# ArduinoDigitalCommsShield.net
KiCad netlist of a schematic drawn in EAGLE
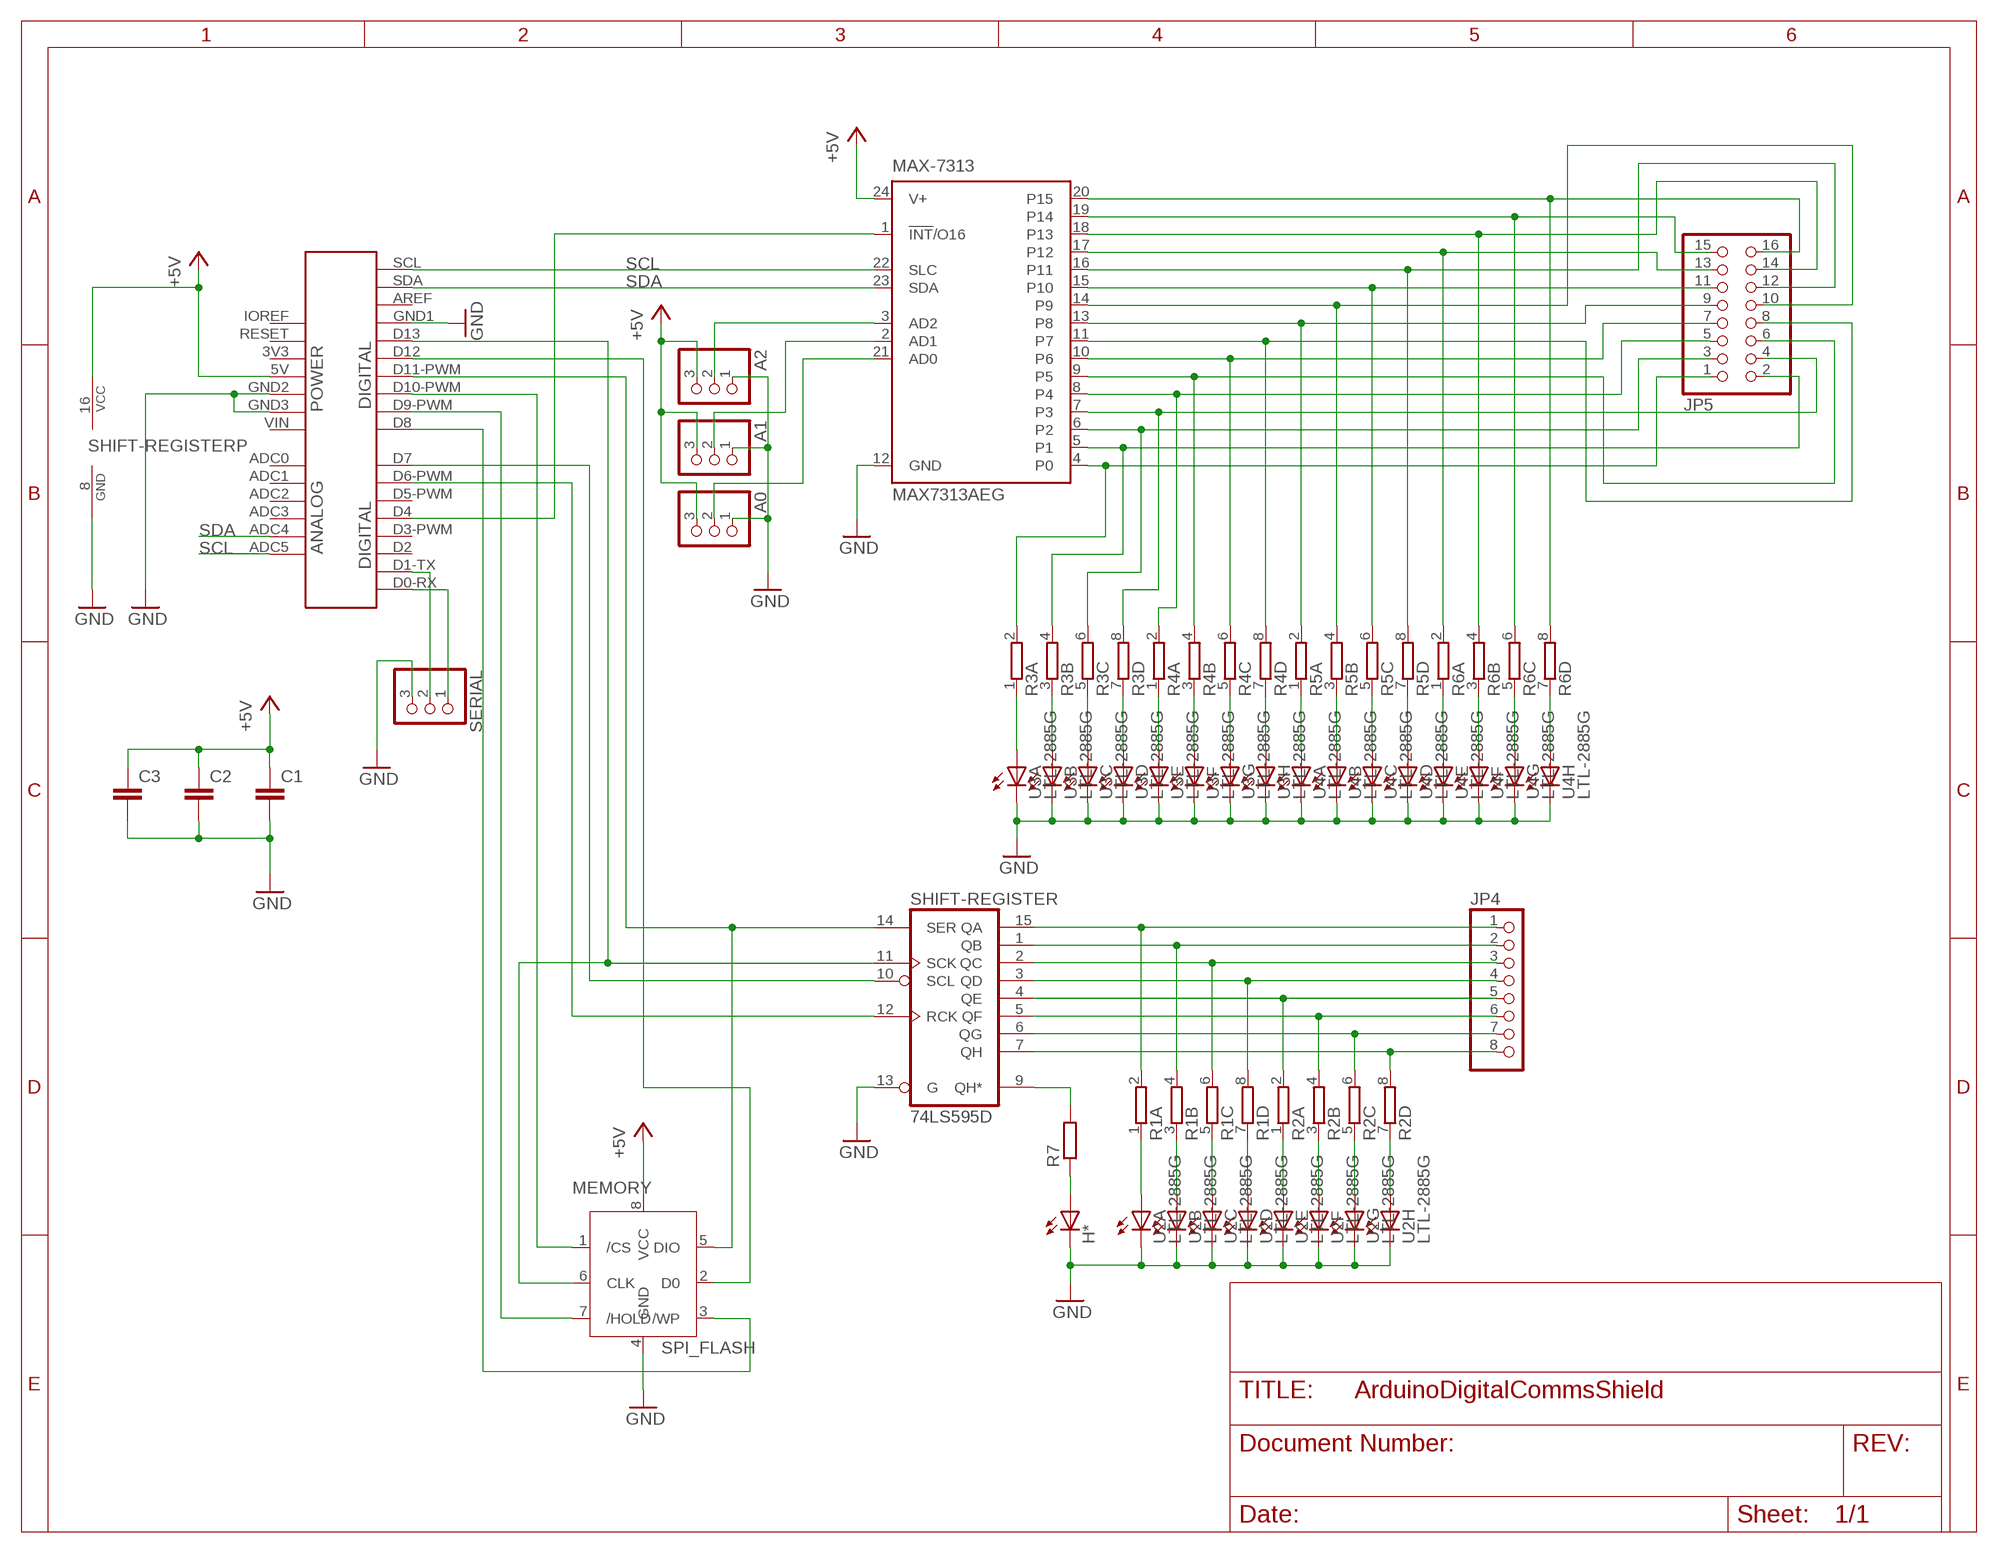
[diagram p0: schematic, sheet 1]

(export (version "E")
  (design (tool "Eeschema 10.0.6"))
  (components
    (comp (ref "A0")
      (value "PINHD-1X3_2.54")
      (footprint "eagle-import:1X03")
      (libsource (lib "eagle-import") (part "PINHD-1X3_2.54"))
    )
    (comp (ref "A1")
      (value "PINHD-1X3_2.54")
      (footprint "eagle-import:1X03")
      (libsource (lib "eagle-import") (part "PINHD-1X3_2.54"))
    )
    (comp (ref "A2")
      (value "PINHD-1X3_2.54")
      (footprint "eagle-import:1X03")
      (libsource (lib "eagle-import") (part "PINHD-1X3_2.54"))
    )
    (comp (ref "ARD1")
      (value "UNO-R3")
      (footprint "eagle-import:UNO-R3")
      (libsource (lib "eagle-import") (part "UNO-R3"))
    )
    (comp (ref "C1")
      (value "C-EUC0603")
      (footprint "eagle-import:C0603")
      (libsource (lib "eagle-import") (part "C-EUC0603"))
    )
    (comp (ref "C2")
      (value "C-EUC0603")
      (footprint "eagle-import:C0603")
      (libsource (lib "eagle-import") (part "C-EUC0603"))
    )
    (comp (ref "C3")
      (value "C-EUC0603")
      (footprint "eagle-import:C0603")
      (libsource (lib "eagle-import") (part "C-EUC0603"))
    )
    (comp (ref "H*")
      (value "LED5MM")
      (footprint "eagle-import:LED5MM")
      (libsource (lib "eagle-import") (part "LED5MM"))
    )
    (comp (ref "JP4")
      (value "PINHD-1X8_2.54")
      (footprint "eagle-import:1X08")
      (libsource (lib "eagle-import") (part "PINHD-1X8_2.54"))
    )
    (comp (ref "JP5")
      (value "PINHD-2X8_2.54")
      (footprint "eagle-import:2X08")
      (libsource (lib "eagle-import") (part "PINHD-2X8_2.54"))
    )
    (comp (ref "MAX-7313")
      (value "MAX7313AEG")
      (footprint "eagle-import:QSOP24")
      (fields (field (name "MPN") "MAX7313AEG+"))
      (libsource (lib "eagle-import") (part "MAX7313AEG"))
    )
    (comp (ref "MEMORY")
      (value "SPI_FLASH")
      (footprint "eagle-import:SOIC-8")
      (libsource (lib "eagle-import") (part "SPI_FLASH"))
    )
    (comp (ref "R1")
      (value "4R-NCTS742C083")
      (footprint "eagle-import:CTS742C083-RES")
      (libsource (lib "eagle-import") (part "4R-NCTS742C083"))
    )
    (comp (ref "R2")
      (value "4R-NCTS742C083")
      (footprint "eagle-import:CTS742C083-RES")
      (libsource (lib "eagle-import") (part "4R-NCTS742C083"))
    )
    (comp (ref "R3")
      (value "4R-NCTS742C083")
      (footprint "eagle-import:CTS742C083-RES")
      (libsource (lib "eagle-import") (part "4R-NCTS742C083"))
    )
    (comp (ref "R4")
      (value "4R-NCTS742C083")
      (footprint "eagle-import:CTS742C083-RES")
      (libsource (lib "eagle-import") (part "4R-NCTS742C083"))
    )
    (comp (ref "R5")
      (value "4R-NCTS742C083")
      (footprint "eagle-import:CTS742C083-RES")
      (libsource (lib "eagle-import") (part "4R-NCTS742C083"))
    )
    (comp (ref "R6")
      (value "4R-NCTS742C083")
      (footprint "eagle-import:CTS742C083-RES")
      (libsource (lib "eagle-import") (part "4R-NCTS742C083"))
    )
    (comp (ref "R7")
      (value "R-EU_R0603")
      (footprint "eagle-import:R0603")
      (libsource (lib "eagle-import") (part "R-EU_R0603"))
    )
    (comp (ref "SERIAL")
      (value "PINHD-1X3_2.54")
      (footprint "eagle-import:1X03")
      (libsource (lib "eagle-import") (part "PINHD-1X3_2.54"))
    )
    (comp (ref "SHIFT-REGISTER")
      (value "74LS595D")
      (footprint "eagle-import:SO16")
      (libsource (lib "eagle-import") (part "74595DLS"))
    )
    (comp (ref "U2")
      (value "LTL-2885G")
      (footprint "eagle-import:LTL-2_85")
      (libsource (lib "eagle-import") (part "LTL-285G8"))
    )
    (comp (ref "U3")
      (value "LTL-2885G")
      (footprint "eagle-import:LTL-2_85")
      (libsource (lib "eagle-import") (part "LTL-285G8"))
    )
    (comp (ref "U4")
      (value "LTL-2885G")
      (footprint "eagle-import:LTL-2_85")
      (libsource (lib "eagle-import") (part "LTL-285G8"))
    )
  )
  (nets
    (net (code "1") (name "+5V") (class "Default")
      (node (ref "A0") (pin "3") (pinfunction "3_3") (pintype "passive"))
      (node (ref "A1") (pin "3") (pinfunction "3_3") (pintype "passive"))
      (node (ref "A2") (pin "3") (pinfunction "3_3") (pintype "passive"))
      (node (ref "ARD1") (pin "5V") (pinfunction "5V_5V") (pintype "bidirectional"))
      (node (ref "C1") (pin "1") (pinfunction "1_1") (pintype "passive"))
      (node (ref "C2") (pin "1") (pinfunction "1_1") (pintype "passive"))
      (node (ref "C3") (pin "1") (pinfunction "1_1") (pintype "passive"))
      (node (ref "MAX-7313") (pin "24") (pinfunction "V+_24") (pintype "power_in"))
      (node (ref "MEMORY") (pin "8") (pinfunction "VCC_8") (pintype "power_in"))
      (node (ref "SHIFT-REGISTER") (pin "16") (pinfunction "VCC_16") (pintype "power_in"))
    )
    (net (code "2") (name "/SCL") (class "Default")
      (node (ref "ARD1") (pin "ADC5") (pinfunction "ADC5_ADC5") (pintype "bidirectional"))
      (node (ref "ARD1") (pin "SCL") (pinfunction "SCL_SCL") (pintype "bidirectional"))
      (node (ref "MAX-7313") (pin "22") (pinfunction "SLC_22") (pintype "input"))
    )
    (net (code "3") (name "/SDA") (class "Default")
      (node (ref "ARD1") (pin "ADC4") (pinfunction "ADC4_ADC4") (pintype "bidirectional"))
      (node (ref "ARD1") (pin "SDA") (pinfunction "SDA_SDA") (pintype "bidirectional"))
      (node (ref "MAX-7313") (pin "23") (pinfunction "SDA_23") (pintype "bidirectional"))
    )
    (net (code "4") (name "GND") (class "Default")
      (node (ref "A0") (pin "1") (pinfunction "1_1") (pintype "passive"))
      (node (ref "A1") (pin "1") (pinfunction "1_1") (pintype "passive"))
      (node (ref "A2") (pin "1") (pinfunction "1_1") (pintype "passive"))
      (node (ref "ARD1") (pin "GND1") (pinfunction "GND1_GND1") (pintype "bidirectional"))
      (node (ref "ARD1") (pin "GND2") (pinfunction "GND2_GND2") (pintype "bidirectional"))
      (node (ref "ARD1") (pin "GND3") (pinfunction "GND3_GND3") (pintype "bidirectional"))
      (node (ref "C1") (pin "2") (pinfunction "2_2") (pintype "passive"))
      (node (ref "C2") (pin "2") (pinfunction "2_2") (pintype "passive"))
      (node (ref "C3") (pin "2") (pinfunction "2_2") (pintype "passive"))
      (node (ref "H*") (pin "K") (pinfunction "C_K") (pintype "passive"))
      (node (ref "MAX-7313") (pin "12") (pinfunction "GND_12") (pintype "power_in"))
      (node (ref "MEMORY") (pin "4") (pinfunction "GND_4") (pintype "power_in"))
      (node (ref "SERIAL") (pin "3") (pinfunction "3_3") (pintype "passive"))
      (node (ref "SHIFT-REGISTER") (pin "13") (pinfunction "G_13") (pintype "input"))
      (node (ref "SHIFT-REGISTER") (pin "8") (pinfunction "GND_8") (pintype "power_in"))
      (node (ref "U2") (pin "1") (pinfunction "C_1") (pintype "passive"))
      (node (ref "U2") (pin "12") (pinfunction "C_12") (pintype "passive"))
      (node (ref "U2") (pin "13") (pinfunction "C_13") (pintype "passive"))
      (node (ref "U2") (pin "16") (pinfunction "C_16") (pintype "passive"))
      (node (ref "U2") (pin "4") (pinfunction "C_4") (pintype "passive"))
      (node (ref "U2") (pin "5") (pinfunction "C_5") (pintype "passive"))
      (node (ref "U2") (pin "8") (pinfunction "C_8") (pintype "passive"))
      (node (ref "U2") (pin "9") (pinfunction "C_9") (pintype "passive"))
      (node (ref "U3") (pin "1") (pinfunction "C_1") (pintype "passive"))
      (node (ref "U3") (pin "12") (pinfunction "C_12") (pintype "passive"))
      (node (ref "U3") (pin "13") (pinfunction "C_13") (pintype "passive"))
      (node (ref "U3") (pin "16") (pinfunction "C_16") (pintype "passive"))
      (node (ref "U3") (pin "4") (pinfunction "C_4") (pintype "passive"))
      (node (ref "U3") (pin "5") (pinfunction "C_5") (pintype "passive"))
      (node (ref "U3") (pin "8") (pinfunction "C_8") (pintype "passive"))
      (node (ref "U3") (pin "9") (pinfunction "C_9") (pintype "passive"))
      (node (ref "U4") (pin "1") (pinfunction "C_1") (pintype "passive"))
      (node (ref "U4") (pin "12") (pinfunction "C_12") (pintype "passive"))
      (node (ref "U4") (pin "13") (pinfunction "C_13") (pintype "passive"))
      (node (ref "U4") (pin "16") (pinfunction "C_16") (pintype "passive"))
      (node (ref "U4") (pin "4") (pinfunction "C_4") (pintype "passive"))
      (node (ref "U4") (pin "5") (pinfunction "C_5") (pintype "passive"))
      (node (ref "U4") (pin "8") (pinfunction "C_8") (pintype "passive"))
      (node (ref "U4") (pin "9") (pinfunction "C_9") (pintype "passive"))
    )
    (net (code "5") (name "Net-(ARD1-D0)") (class "Default")
      (node (ref "ARD1") (pin "D0-RX") (pinfunction "D0_D0-RX") (pintype "bidirectional"))
      (node (ref "SERIAL") (pin "1") (pinfunction "1_1") (pintype "passive"))
    )
    (net (code "6") (name "Net-(ARD1-D1)") (class "Default")
      (node (ref "ARD1") (pin "D1-TX") (pinfunction "D1_D1-TX") (pintype "bidirectional"))
      (node (ref "SERIAL") (pin "2") (pinfunction "2_2") (pintype "passive"))
    )
    (net (code "7") (name "Net-(ARD1-D6)") (class "Default")
      (node (ref "ARD1") (pin "D6-PWM") (pinfunction "D6_D6-PWM") (pintype "bidirectional"))
      (node (ref "SHIFT-REGISTER") (pin "12") (pinfunction "RCK_12") (pintype "input"))
    )
    (net (code "8") (name "Net-(ARD1-D9)") (class "Default")
      (node (ref "ARD1") (pin "D9-PWM") (pinfunction "D9_D9-PWM") (pintype "bidirectional"))
      (node (ref "MEMORY") (pin "7") (pinfunction "/HOLD_7") (pintype "input"))
    )
    (net (code "9") (name "Net-(ARD1-D10)") (class "Default")
      (node (ref "ARD1") (pin "D10-PWM") (pinfunction "D10_D10-PWM") (pintype "bidirectional"))
      (node (ref "MEMORY") (pin "1") (pinfunction "/CS_1") (pintype "input"))
    )
    (net (code "10") (name "Net-(ARD1-D11)") (class "Default")
      (node (ref "ARD1") (pin "D11-PWM") (pinfunction "D11_D11-PWM") (pintype "bidirectional"))
      (node (ref "MEMORY") (pin "5") (pinfunction "DIO_5") (pintype "bidirectional"))
      (node (ref "SHIFT-REGISTER") (pin "14") (pinfunction "SER_14") (pintype "input"))
    )
    (net (code "11") (name "Net-(H*-PadA)") (class "Default")
      (node (ref "H*") (pin "A") (pinfunction "A_A") (pintype "passive"))
      (node (ref "R7") (pin "1") (pinfunction "1_1") (pintype "passive"))
    )
    (net (code "12") (name "Net-(MAX-7313-AD0)") (class "Default")
      (node (ref "A0") (pin "2") (pinfunction "2_2") (pintype "passive"))
      (node (ref "MAX-7313") (pin "21") (pinfunction "AD0_21") (pintype "input"))
    )
    (net (code "13") (name "Net-(MAX-7313-AD1)") (class "Default")
      (node (ref "A1") (pin "2") (pinfunction "2_2") (pintype "passive"))
      (node (ref "MAX-7313") (pin "2") (pinfunction "AD1_2") (pintype "input"))
    )
    (net (code "14") (name "Net-(MAX-7313-AD2)") (class "Default")
      (node (ref "A2") (pin "2") (pinfunction "2_2") (pintype "passive"))
      (node (ref "MAX-7313") (pin "3") (pinfunction "AD2_3") (pintype "input"))
    )
    (net (code "15") (name "Net-(MAX-7313-P0)") (class "Default")
      (node (ref "JP5") (pin "1") (pinfunction "1_1") (pintype "passive"))
      (node (ref "MAX-7313") (pin "4") (pinfunction "P0_4") (pintype "bidirectional"))
      (node (ref "R3") (pin "2") (pinfunction "2_2") (pintype "passive"))
    )
    (net (code "16") (name "Net-(MAX-7313-P1)") (class "Default")
      (node (ref "JP5") (pin "2") (pinfunction "2_2") (pintype "passive"))
      (node (ref "MAX-7313") (pin "5") (pinfunction "P1_5") (pintype "bidirectional"))
      (node (ref "R3") (pin "4") (pinfunction "2_4") (pintype "passive"))
    )
    (net (code "17") (name "Net-(MAX-7313-P2)") (class "Default")
      (node (ref "JP5") (pin "3") (pinfunction "3_3") (pintype "passive"))
      (node (ref "MAX-7313") (pin "6") (pinfunction "P2_6") (pintype "bidirectional"))
      (node (ref "R3") (pin "6") (pinfunction "2_6") (pintype "passive"))
    )
    (net (code "18") (name "Net-(MAX-7313-P3)") (class "Default")
      (node (ref "JP5") (pin "4") (pinfunction "4_4") (pintype "passive"))
      (node (ref "MAX-7313") (pin "7") (pinfunction "P3_7") (pintype "bidirectional"))
      (node (ref "R3") (pin "8") (pinfunction "2_8") (pintype "passive"))
    )
    (net (code "19") (name "Net-(MAX-7313-P4)") (class "Default")
      (node (ref "JP5") (pin "5") (pinfunction "5_5") (pintype "passive"))
      (node (ref "MAX-7313") (pin "8") (pinfunction "P4_8") (pintype "bidirectional"))
      (node (ref "R4") (pin "2") (pinfunction "2_2") (pintype "passive"))
    )
    (net (code "20") (name "Net-(MAX-7313-P5)") (class "Default")
      (node (ref "JP5") (pin "6") (pinfunction "6_6") (pintype "passive"))
      (node (ref "MAX-7313") (pin "9") (pinfunction "P5_9") (pintype "bidirectional"))
      (node (ref "R4") (pin "4") (pinfunction "2_4") (pintype "passive"))
    )
    (net (code "21") (name "Net-(MAX-7313-P6)") (class "Default")
      (node (ref "JP5") (pin "7") (pinfunction "7_7") (pintype "passive"))
      (node (ref "MAX-7313") (pin "10") (pinfunction "P6_10") (pintype "bidirectional"))
      (node (ref "R4") (pin "6") (pinfunction "2_6") (pintype "passive"))
    )
    (net (code "22") (name "Net-(MAX-7313-P7)") (class "Default")
      (node (ref "JP5") (pin "8") (pinfunction "8_8") (pintype "passive"))
      (node (ref "MAX-7313") (pin "11") (pinfunction "P7_11") (pintype "bidirectional"))
      (node (ref "R4") (pin "8") (pinfunction "2_8") (pintype "passive"))
    )
    (net (code "23") (name "Net-(MAX-7313-P8)") (class "Default")
      (node (ref "JP5") (pin "9") (pinfunction "9_9") (pintype "passive"))
      (node (ref "MAX-7313") (pin "13") (pinfunction "P8_13") (pintype "bidirectional"))
      (node (ref "R5") (pin "2") (pinfunction "2_2") (pintype "passive"))
    )
    (net (code "24") (name "Net-(MAX-7313-P9)") (class "Default")
      (node (ref "JP5") (pin "10") (pinfunction "10_10") (pintype "passive"))
      (node (ref "MAX-7313") (pin "14") (pinfunction "P9_14") (pintype "bidirectional"))
      (node (ref "R5") (pin "4") (pinfunction "2_4") (pintype "passive"))
    )
    (net (code "25") (name "Net-(MAX-7313-P10)") (class "Default")
      (node (ref "JP5") (pin "11") (pinfunction "11_11") (pintype "passive"))
      (node (ref "MAX-7313") (pin "15") (pinfunction "P10_15") (pintype "bidirectional"))
      (node (ref "R5") (pin "6") (pinfunction "2_6") (pintype "passive"))
    )
    (net (code "26") (name "Net-(MAX-7313-P11)") (class "Default")
      (node (ref "JP5") (pin "12") (pinfunction "12_12") (pintype "passive"))
      (node (ref "MAX-7313") (pin "16") (pinfunction "P11_16") (pintype "bidirectional"))
      (node (ref "R5") (pin "8") (pinfunction "2_8") (pintype "passive"))
    )
    (net (code "27") (name "Net-(MAX-7313-P12)") (class "Default")
      (node (ref "JP5") (pin "13") (pinfunction "13_13") (pintype "passive"))
      (node (ref "MAX-7313") (pin "17") (pinfunction "P12_17") (pintype "bidirectional"))
      (node (ref "R6") (pin "2") (pinfunction "2_2") (pintype "passive"))
    )
    (net (code "28") (name "Net-(MAX-7313-P13)") (class "Default")
      (node (ref "JP5") (pin "14") (pinfunction "14_14") (pintype "passive"))
      (node (ref "MAX-7313") (pin "18") (pinfunction "P13_18") (pintype "bidirectional"))
      (node (ref "R6") (pin "4") (pinfunction "2_4") (pintype "passive"))
    )
    (net (code "29") (name "Net-(MAX-7313-P14)") (class "Default")
      (node (ref "JP5") (pin "15") (pinfunction "15_15") (pintype "passive"))
      (node (ref "MAX-7313") (pin "19") (pinfunction "P14_19") (pintype "bidirectional"))
      (node (ref "R6") (pin "6") (pinfunction "2_6") (pintype "passive"))
    )
    (net (code "30") (name "Net-(MAX-7313-P15)") (class "Default")
      (node (ref "JP5") (pin "16") (pinfunction "16_16") (pintype "passive"))
      (node (ref "MAX-7313") (pin "20") (pinfunction "P15_20") (pintype "bidirectional"))
      (node (ref "R6") (pin "8") (pinfunction "2_8") (pintype "passive"))
    )
    (net (code "31") (name "Net-(MAX-7313-~{INT}{slash}O16)") (class "Default")
      (node (ref "ARD1") (pin "D4") (pinfunction "D4_D4") (pintype "bidirectional"))
      (node (ref "MAX-7313") (pin "1") (pinfunction "~{INT}/O16_1") (pintype "open_collector"))
    )
    (net (code "32") (name "Net-(MEMORY-CLK)") (class "Default")
      (node (ref "ARD1") (pin "D13") (pinfunction "D13_D13") (pintype "bidirectional"))
      (node (ref "MEMORY") (pin "6") (pinfunction "CLK_6") (pintype "input"))
      (node (ref "SHIFT-REGISTER") (pin "11") (pinfunction "SCK_11") (pintype "input"))
    )
    (net (code "33") (name "Net-(MEMORY-D0)") (class "Default")
      (node (ref "ARD1") (pin "D12") (pinfunction "D12_D12") (pintype "bidirectional"))
      (node (ref "MEMORY") (pin "2") (pinfunction "D0_2") (pintype "output"))
    )
    (net (code "34") (name "Net-(MEMORY-{slash}WP)") (class "Default")
      (node (ref "ARD1") (pin "D8") (pinfunction "D8_D8") (pintype "bidirectional"))
      (node (ref "MEMORY") (pin "3") (pinfunction "/WP_3") (pintype "input"))
    )
    (net (code "35") (name "Net-(R1B-1)") (class "Default")
      (node (ref "R1") (pin "3") (pinfunction "1_3") (pintype "passive"))
      (node (ref "U2") (pin "3") (pinfunction "A_3") (pintype "passive"))
    )
    (net (code "36") (name "Net-(R1B-2)") (class "Default")
      (node (ref "JP4") (pin "2") (pinfunction "2_2") (pintype "passive"))
      (node (ref "R1") (pin "4") (pinfunction "2_4") (pintype "passive"))
      (node (ref "SHIFT-REGISTER") (pin "1") (pinfunction "QB_1") (pintype "tri_state"))
    )
    (net (code "37") (name "Net-(R1C-1)") (class "Default")
      (node (ref "R1") (pin "5") (pinfunction "1_5") (pintype "passive"))
      (node (ref "U2") (pin "6") (pinfunction "A_6") (pintype "passive"))
    )
    (net (code "38") (name "Net-(R1C-2)") (class "Default")
      (node (ref "JP4") (pin "3") (pinfunction "3_3") (pintype "passive"))
      (node (ref "R1") (pin "6") (pinfunction "2_6") (pintype "passive"))
      (node (ref "SHIFT-REGISTER") (pin "2") (pinfunction "QC_2") (pintype "tri_state"))
    )
    (net (code "39") (name "Net-(R1D-1)") (class "Default")
      (node (ref "R1") (pin "7") (pinfunction "1_7") (pintype "passive"))
      (node (ref "U2") (pin "7") (pinfunction "A_7") (pintype "passive"))
    )
    (net (code "40") (name "Net-(R1D-2)") (class "Default")
      (node (ref "JP4") (pin "4") (pinfunction "4_4") (pintype "passive"))
      (node (ref "R1") (pin "8") (pinfunction "2_8") (pintype "passive"))
      (node (ref "SHIFT-REGISTER") (pin "3") (pinfunction "QD_3") (pintype "tri_state"))
    )
    (net (code "41") (name "Net-(R2B-1)") (class "Default")
      (node (ref "R2") (pin "3") (pinfunction "1_3") (pintype "passive"))
      (node (ref "U2") (pin "11") (pinfunction "A_11") (pintype "passive"))
    )
    (net (code "42") (name "Net-(R2B-2)") (class "Default")
      (node (ref "JP4") (pin "6") (pinfunction "6_6") (pintype "passive"))
      (node (ref "R2") (pin "4") (pinfunction "2_4") (pintype "passive"))
      (node (ref "SHIFT-REGISTER") (pin "5") (pinfunction "QF_5") (pintype "tri_state"))
    )
    (net (code "43") (name "Net-(R2C-1)") (class "Default")
      (node (ref "R2") (pin "5") (pinfunction "1_5") (pintype "passive"))
      (node (ref "U2") (pin "14") (pinfunction "A_14") (pintype "passive"))
    )
    (net (code "44") (name "Net-(R2C-2)") (class "Default")
      (node (ref "JP4") (pin "7") (pinfunction "7_7") (pintype "passive"))
      (node (ref "R2") (pin "6") (pinfunction "2_6") (pintype "passive"))
      (node (ref "SHIFT-REGISTER") (pin "6") (pinfunction "QG_6") (pintype "tri_state"))
    )
    (net (code "45") (name "Net-(R2D-1)") (class "Default")
      (node (ref "R2") (pin "7") (pinfunction "1_7") (pintype "passive"))
      (node (ref "U2") (pin "15") (pinfunction "A_15") (pintype "passive"))
    )
    (net (code "46") (name "Net-(R2D-2)") (class "Default")
      (node (ref "JP4") (pin "8") (pinfunction "8_8") (pintype "passive"))
      (node (ref "R2") (pin "8") (pinfunction "2_8") (pintype "passive"))
      (node (ref "SHIFT-REGISTER") (pin "7") (pinfunction "QH_7") (pintype "tri_state"))
    )
    (net (code "47") (name "Net-(R3B-1)") (class "Default")
      (node (ref "R3") (pin "3") (pinfunction "1_3") (pintype "passive"))
      (node (ref "U3") (pin "3") (pinfunction "A_3") (pintype "passive"))
    )
    (net (code "48") (name "Net-(R3C-1)") (class "Default")
      (node (ref "R3") (pin "5") (pinfunction "1_5") (pintype "passive"))
      (node (ref "U3") (pin "6") (pinfunction "A_6") (pintype "passive"))
    )
    (net (code "49") (name "Net-(R3D-1)") (class "Default")
      (node (ref "R3") (pin "7") (pinfunction "1_7") (pintype "passive"))
      (node (ref "U3") (pin "7") (pinfunction "A_7") (pintype "passive"))
    )
    (net (code "50") (name "Net-(R4B-1)") (class "Default")
      (node (ref "R4") (pin "3") (pinfunction "1_3") (pintype "passive"))
      (node (ref "U3") (pin "11") (pinfunction "A_11") (pintype "passive"))
    )
    (net (code "51") (name "Net-(R4C-1)") (class "Default")
      (node (ref "R4") (pin "5") (pinfunction "1_5") (pintype "passive"))
      (node (ref "U3") (pin "14") (pinfunction "A_14") (pintype "passive"))
    )
    (net (code "52") (name "Net-(R4D-1)") (class "Default")
      (node (ref "R4") (pin "7") (pinfunction "1_7") (pintype "passive"))
      (node (ref "U3") (pin "15") (pinfunction "A_15") (pintype "passive"))
    )
    (net (code "53") (name "Net-(R5B-1)") (class "Default")
      (node (ref "R5") (pin "3") (pinfunction "1_3") (pintype "passive"))
      (node (ref "U4") (pin "3") (pinfunction "A_3") (pintype "passive"))
    )
    (net (code "54") (name "Net-(R5C-1)") (class "Default")
      (node (ref "R5") (pin "5") (pinfunction "1_5") (pintype "passive"))
      (node (ref "U4") (pin "6") (pinfunction "A_6") (pintype "passive"))
    )
    (net (code "55") (name "Net-(R5D-1)") (class "Default")
      (node (ref "R5") (pin "7") (pinfunction "1_7") (pintype "passive"))
      (node (ref "U4") (pin "7") (pinfunction "A_7") (pintype "passive"))
    )
    (net (code "56") (name "Net-(R6B-1)") (class "Default")
      (node (ref "R6") (pin "3") (pinfunction "1_3") (pintype "passive"))
      (node (ref "U4") (pin "11") (pinfunction "A_11") (pintype "passive"))
    )
    (net (code "57") (name "Net-(R6C-1)") (class "Default")
      (node (ref "R6") (pin "5") (pinfunction "1_5") (pintype "passive"))
      (node (ref "U4") (pin "14") (pinfunction "A_14") (pintype "passive"))
    )
    (net (code "58") (name "Net-(R6D-1)") (class "Default")
      (node (ref "R6") (pin "7") (pinfunction "1_7") (pintype "passive"))
      (node (ref "U4") (pin "15") (pinfunction "A_15") (pintype "passive"))
    )
    (net (code "59") (name "Net-(SHIFT-REGISTERA-QA)") (class "Default")
      (node (ref "JP4") (pin "1") (pinfunction "1_1") (pintype "passive"))
      (node (ref "R1") (pin "2") (pinfunction "2_2") (pintype "passive"))
      (node (ref "SHIFT-REGISTER") (pin "15") (pinfunction "QA_15") (pintype "tri_state"))
    )
    (net (code "60") (name "Net-(SHIFT-REGISTERA-QE)") (class "Default")
      (node (ref "JP4") (pin "5") (pinfunction "5_5") (pintype "passive"))
      (node (ref "R2") (pin "2") (pinfunction "2_2") (pintype "passive"))
      (node (ref "SHIFT-REGISTER") (pin "4") (pinfunction "QE_4") (pintype "tri_state"))
    )
    (net (code "61") (name "Net-(SHIFT-REGISTERA-QH*)") (class "Default")
      (node (ref "R7") (pin "2") (pinfunction "2_2") (pintype "passive"))
      (node (ref "SHIFT-REGISTER") (pin "9") (pinfunction "QH*_9") (pintype "tri_state"))
    )
    (net (code "62") (name "Net-(SHIFT-REGISTERA-SCL)") (class "Default")
      (node (ref "ARD1") (pin "D7") (pinfunction "D7_D7") (pintype "bidirectional"))
      (node (ref "SHIFT-REGISTER") (pin "10") (pinfunction "SCL_10") (pintype "input"))
    )
    (net (code "63") (name "Net-(U2A-A)") (class "Default")
      (node (ref "R1") (pin "1") (pinfunction "1_1") (pintype "passive"))
      (node (ref "U2") (pin "2") (pinfunction "A_2") (pintype "passive"))
    )
    (net (code "64") (name "Net-(U2E-A)") (class "Default")
      (node (ref "R2") (pin "1") (pinfunction "1_1") (pintype "passive"))
      (node (ref "U2") (pin "10") (pinfunction "A_10") (pintype "passive"))
    )
    (net (code "65") (name "Net-(U3A-A)") (class "Default")
      (node (ref "R3") (pin "1") (pinfunction "1_1") (pintype "passive"))
      (node (ref "U3") (pin "2") (pinfunction "A_2") (pintype "passive"))
    )
    (net (code "66") (name "Net-(U3E-A)") (class "Default")
      (node (ref "R4") (pin "1") (pinfunction "1_1") (pintype "passive"))
      (node (ref "U3") (pin "10") (pinfunction "A_10") (pintype "passive"))
    )
    (net (code "67") (name "Net-(U4A-A)") (class "Default")
      (node (ref "R5") (pin "1") (pinfunction "1_1") (pintype "passive"))
      (node (ref "U4") (pin "2") (pinfunction "A_2") (pintype "passive"))
    )
    (net (code "68") (name "Net-(U4E-A)") (class "Default")
      (node (ref "R6") (pin "1") (pinfunction "1_1") (pintype "passive"))
      (node (ref "U4") (pin "10") (pinfunction "A_10") (pintype "passive"))
    )
    (net (code "69") (name "unconnected-(ARD1-D3-PadD3-PWM)") (class "Default")
      (node (ref "ARD1") (pin "D3-PWM") (pinfunction "D3_D3-PWM") (pintype "bidirectional"))
    )
    (net (code "70") (name "unconnected-(ARD1-D5-PadD5-PWM)") (class "Default")
      (node (ref "ARD1") (pin "D5-PWM") (pinfunction "D5_D5-PWM") (pintype "bidirectional"))
    )
    (net (code "71") (name "unconnected-(ARD1-Pad3V3)") (class "Default")
      (node (ref "ARD1") (pin "3V3") (pinfunction "3V3_3V3") (pintype "bidirectional"))
    )
    (net (code "72") (name "unconnected-(ARD1-PadADC0)") (class "Default")
      (node (ref "ARD1") (pin "ADC0") (pinfunction "ADC0_ADC0") (pintype "bidirectional"))
    )
    (net (code "73") (name "unconnected-(ARD1-PadADC1)") (class "Default")
      (node (ref "ARD1") (pin "ADC1") (pinfunction "ADC1_ADC1") (pintype "bidirectional"))
    )
    (net (code "74") (name "unconnected-(ARD1-PadADC2)") (class "Default")
      (node (ref "ARD1") (pin "ADC2") (pinfunction "ADC2_ADC2") (pintype "bidirectional"))
    )
    (net (code "75") (name "unconnected-(ARD1-PadADC3)") (class "Default")
      (node (ref "ARD1") (pin "ADC3") (pinfunction "ADC3_ADC3") (pintype "bidirectional"))
    )
    (net (code "76") (name "unconnected-(ARD1-PadAREF)") (class "Default")
      (node (ref "ARD1") (pin "AREF") (pinfunction "AREF_AREF") (pintype "bidirectional"))
    )
    (net (code "77") (name "unconnected-(ARD1-PadD2)") (class "Default")
      (node (ref "ARD1") (pin "D2") (pinfunction "D2_D2") (pintype "bidirectional"))
    )
    (net (code "78") (name "unconnected-(ARD1-PadIOREF)") (class "Default")
      (node (ref "ARD1") (pin "IOREF") (pinfunction "IOREF_IOREF") (pintype "bidirectional"))
    )
    (net (code "79") (name "unconnected-(ARD1-PadRESET)") (class "Default")
      (node (ref "ARD1") (pin "RESET") (pinfunction "RESET_RESET") (pintype "bidirectional"))
    )
    (net (code "80") (name "unconnected-(ARD1-PadVIN)") (class "Default")
      (node (ref "ARD1") (pin "VIN") (pinfunction "VIN_VIN") (pintype "bidirectional"))
    )
  )
)
